# ProDoc_simpleCH552_typeA_start.net
KiCad netlist of a schematic drawn in EasyEDA Pro
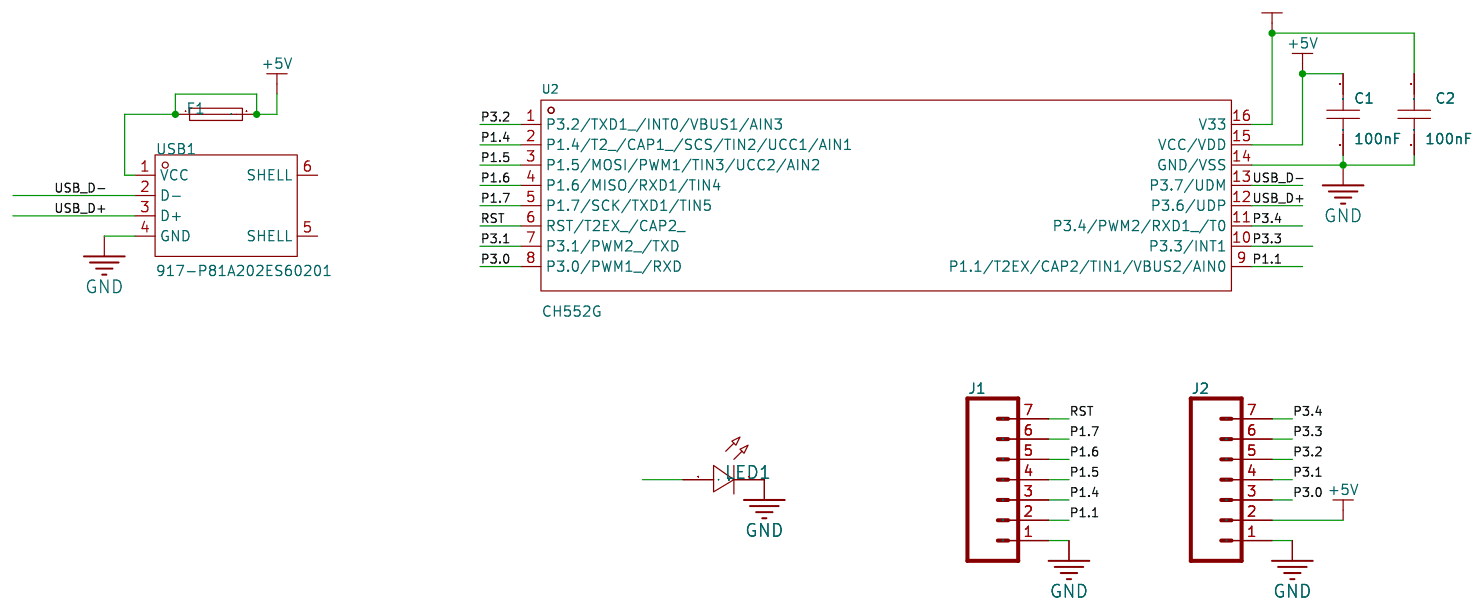
[diagram p0: schematic sheet]

(export (version "E")
  (design (tool "Eeschema 10.0.6"))
  (components
    (comp (ref "C1")
      (value "100nF")
      (footprint "easyedapro:C0805")
      (libsource (lib "easyedapro") (part "CAP"))
    )
    (comp (ref "C2")
      (value "100nF")
      (footprint "easyedapro:C0805")
      (libsource (lib "easyedapro") (part "CAP"))
    )
    (comp (ref "F1")
      (value "SF-1206S080-2")
      (footprint "easyedapro:F1206")
      (fields (field (name "Manufacturer") "BOURNS"))
      (libsource (lib "easyedapro") (part "SF-1206S080-2"))
    )
    (comp (ref "J1")
      (value "CONN_07NO_SILK")
      (footprint "easyedapro:1X07_NO_SILK")
      (libsource (lib "easyedapro") (part "SparkFun-Connectors_CONN_07_NO_SILK"))
    )
    (comp (ref "J2")
      (value "CONN_07NO_SILK")
      (footprint "easyedapro:1X07_NO_SILK")
      (libsource (lib "easyedapro") (part "SparkFun-Connectors_CONN_07_NO_SILK"))
    )
    (comp (ref "LED1")
      (value "~")
      (footprint "easyedapro:LED0805-RD_GREEN")
      (libsource (lib "easyedapro") (part "LED_R"))
    )
    (comp (ref "U2")
      (value "CH552G")
      (footprint "easyedapro:SOP-16_L10.0-W3.9-P1.27-LS6.0-BL")
      (fields (field (name "Manufacturer") "WCH(南京沁恒)"))
      (libsource (lib "easyedapro") (part "CH552G"))
    )
    (comp (ref "USB1")
      (value "917-P81A202ES60201")
      (footprint "easyedapro:USB-A-SMD_917-P81A202ES60201")
      (fields (field (name "Manufacturer") "精拓金"))
      (libsource (lib "easyedapro") (part "917-P81A202ES60201"))
    )
  )
  (nets
    (net (code "1") (name "+5V") (class "Default")
      (node (ref "C1") (pin "1") (pinfunction "1_1") (pintype "input"))
      (node (ref "F1") (pin "1") (pinfunction "1_1") (pintype "unspecified"))
      (node (ref "F1") (pin "2") (pinfunction "2_2") (pintype "unspecified"))
      (node (ref "J2") (pin "2") (pinfunction "2_2") (pintype "unspecified"))
      (node (ref "U2") (pin "15") (pinfunction "VCC/VDD_15") (pintype "input"))
      (node (ref "USB1") (pin "1") (pinfunction "VCC_1") (pintype "unspecified"))
    )
    (net (code "2") (name "/P1.1") (class "Default")
      (node (ref "J1") (pin "2") (pinfunction "2_2") (pintype "unspecified"))
      (node (ref "U2") (pin "9") (pinfunction "P1.1/T2EX/CAP2/TIN1/VBUS2/AIN0_9") (pintype "input"))
    )
    (net (code "3") (name "/P1.4") (class "Default")
      (node (ref "J1") (pin "3") (pinfunction "3_3") (pintype "unspecified"))
      (node (ref "U2") (pin "2") (pinfunction "P1.4/T2_/CAP1_/SCS/TIN2/UCC1/AIN1_2") (pintype "input"))
    )
    (net (code "4") (name "/P1.5") (class "Default")
      (node (ref "J1") (pin "4") (pinfunction "4_4") (pintype "unspecified"))
      (node (ref "U2") (pin "3") (pinfunction "P1.5/MOSI/PWM1/TIN3/UCC2/AIN2_3") (pintype "input"))
    )
    (net (code "5") (name "/P1.6") (class "Default")
      (node (ref "J1") (pin "5") (pinfunction "5_5") (pintype "unspecified"))
      (node (ref "U2") (pin "4") (pinfunction "P1.6/MISO/RXD1/TIN4_4") (pintype "input"))
    )
    (net (code "6") (name "/P1.7") (class "Default")
      (node (ref "J1") (pin "6") (pinfunction "6_6") (pintype "unspecified"))
      (node (ref "U2") (pin "5") (pinfunction "P1.7/SCK/TXD1/TIN5_5") (pintype "input"))
    )
    (net (code "7") (name "/P3.0") (class "Default")
      (node (ref "J2") (pin "3") (pinfunction "3_3") (pintype "unspecified"))
      (node (ref "U2") (pin "8") (pinfunction "P3.0/PWM1_/RXD_8") (pintype "input"))
    )
    (net (code "8") (name "/P3.1") (class "Default")
      (node (ref "J2") (pin "4") (pinfunction "4_4") (pintype "unspecified"))
      (node (ref "U2") (pin "7") (pinfunction "P3.1/PWM2_/TXD_7") (pintype "input"))
    )
    (net (code "9") (name "/P3.2") (class "Default")
      (node (ref "J2") (pin "5") (pinfunction "5_5") (pintype "unspecified"))
      (node (ref "U2") (pin "1") (pinfunction "P3.2/TXD1_/INT0/VBUS1/AIN3_1") (pintype "input"))
    )
    (net (code "10") (name "/P3.3") (class "Default")
      (node (ref "J2") (pin "6") (pinfunction "6_6") (pintype "unspecified"))
      (node (ref "U2") (pin "10") (pinfunction "P3.3/INT1_10") (pintype "input"))
    )
    (net (code "11") (name "/P3.4") (class "Default")
      (node (ref "J2") (pin "7") (pinfunction "7_7") (pintype "unspecified"))
      (node (ref "U2") (pin "11") (pinfunction "P3.4/PWM2/RXD1_/T0_11") (pintype "input"))
    )
    (net (code "12") (name "/RST") (class "Default")
      (node (ref "J1") (pin "7") (pinfunction "7_7") (pintype "unspecified"))
      (node (ref "U2") (pin "6") (pinfunction "RST/T2EX_/CAP2__6") (pintype "input"))
    )
    (net (code "13") (name "/USB_D+") (class "Default")
      (node (ref "U2") (pin "12") (pinfunction "P3.6/UDP_12") (pintype "input"))
      (node (ref "USB1") (pin "3") (pinfunction "D+_3") (pintype "unspecified"))
    )
    (net (code "14") (name "/USB_D-") (class "Default")
      (node (ref "U2") (pin "13") (pinfunction "P3.7/UDM_13") (pintype "input"))
      (node (ref "USB1") (pin "2") (pinfunction "D-_2") (pintype "unspecified"))
    )
    (net (code "15") (name "3.3V") (class "Default")
      (node (ref "C2") (pin "1") (pinfunction "1_1") (pintype "input"))
      (node (ref "U2") (pin "16") (pinfunction "V33_16") (pintype "input"))
    )
    (net (code "16") (name "GND") (class "Default")
      (node (ref "C1") (pin "2") (pinfunction "2_2") (pintype "input"))
      (node (ref "C2") (pin "2") (pinfunction "2_2") (pintype "input"))
      (node (ref "J1") (pin "1") (pinfunction "1_1") (pintype "unspecified"))
      (node (ref "J2") (pin "1") (pinfunction "1_1") (pintype "unspecified"))
      (node (ref "LED1") (pin "1") (pinfunction "C_1") (pintype "input"))
      (node (ref "U2") (pin "14") (pinfunction "GND/VSS_14") (pintype "input"))
      (node (ref "USB1") (pin "4") (pinfunction "GND_4") (pintype "unspecified"))
    )
    (net (code "17") (name "unconnected-(LED1-A-Pad2)") (class "Default")
      (node (ref "LED1") (pin "2") (pinfunction "A_2") (pintype "input"))
    )
    (net (code "18") (name "unconnected-(USB1-SHELL-Pad5)") (class "Default")
      (node (ref "USB1") (pin "5") (pinfunction "SHELL_5") (pintype "unspecified"))
    )
    (net (code "19") (name "unconnected-(USB1-SHELL-Pad6)") (class "Default")
      (node (ref "USB1") (pin "6") (pinfunction "SHELL_6") (pintype "unspecified"))
    )
  )
)
